# TemperatureModule.net
KiCad netlist of a schematic drawn in EAGLE
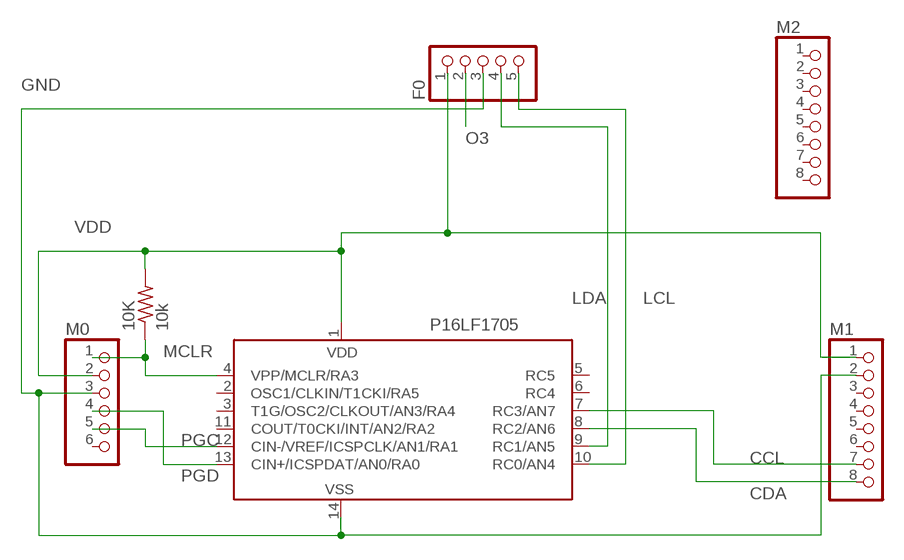
[diagram p0: schematic, sheet 1]

(export (version "E")
  (design (tool "Eeschema 10.0.6"))
  (components
    (comp (ref "10K")
      (value "10k")
      (footprint "eagle-import:0204_7")
      (libsource (lib "eagle-import") (part "R-US_0204/7"))
    )
    (comp (ref "F0")
      (value "PINHD-1X5")
      (footprint "eagle-import:1X05")
      (libsource (lib "eagle-import") (part "PINHD-1X5"))
    )
    (comp (ref "M0")
      (value "PINHD-1X6")
      (footprint "eagle-import:1X06")
      (libsource (lib "eagle-import") (part "PINHD-1X6"))
    )
    (comp (ref "M1")
      (value "PINHD-1X8")
      (footprint "eagle-import:1X08")
      (libsource (lib "eagle-import") (part "PINHD-1X8"))
    )
    (comp (ref "M2")
      (value "PINHD-1X8")
      (footprint "eagle-import:1X08")
      (libsource (lib "eagle-import") (part "PINHD-1X8"))
    )
    (comp (ref "P16LF1705")
      (value "PIC16F676SL")
      (footprint "eagle-import:SO-14")
      (fields (field (name "MF") "MICROCHIP") (field (name "MPN") "PIC16F676-I/SL"))
      (libsource (lib "eagle-import") (part "PIC16F676SL"))
    )
  )
  (nets
    (net (code "1") (name "/CCL") (class "Default")
      (node (ref "M1") (pin "7") (pinfunction "7_7") (pintype "passive"))
      (node (ref "P16LF1705") (pin "7") (pinfunction "RC3/AN7_7") (pintype "bidirectional"))
    )
    (net (code "2") (name "/CDA") (class "Default")
      (node (ref "M1") (pin "8") (pinfunction "8_8") (pintype "passive"))
      (node (ref "P16LF1705") (pin "8") (pinfunction "RC2/AN6_8") (pintype "bidirectional"))
    )
    (net (code "3") (name "/GND") (class "Default")
      (node (ref "F0") (pin "3") (pinfunction "3_3") (pintype "passive"))
      (node (ref "M0") (pin "3") (pinfunction "3_3") (pintype "passive"))
      (node (ref "M1") (pin "2") (pinfunction "2_2") (pintype "passive"))
      (node (ref "P16LF1705") (pin "14") (pinfunction "VSS_14") (pintype "power_in"))
    )
    (net (code "4") (name "/LCL") (class "Default")
      (node (ref "F0") (pin "5") (pinfunction "5_5") (pintype "passive"))
      (node (ref "P16LF1705") (pin "10") (pinfunction "RC0/AN4_10") (pintype "bidirectional"))
    )
    (net (code "5") (name "/LDA") (class "Default")
      (node (ref "F0") (pin "4") (pinfunction "4_4") (pintype "passive"))
      (node (ref "P16LF1705") (pin "9") (pinfunction "RC1/AN5_9") (pintype "bidirectional"))
    )
    (net (code "6") (name "/MCLR") (class "Default")
      (node (ref "10K") (pin "1") (pinfunction "1_1") (pintype "passive"))
      (node (ref "M0") (pin "1") (pinfunction "1_1") (pintype "passive"))
      (node (ref "P16LF1705") (pin "4") (pinfunction "VPP/MCLR/RA3_4") (pintype "input"))
    )
    (net (code "7") (name "/O3") (class "Default")
      (node (ref "F0") (pin "2") (pinfunction "2_2") (pintype "passive"))
    )
    (net (code "8") (name "/PGC") (class "Default")
      (node (ref "M0") (pin "5") (pinfunction "5_5") (pintype "passive"))
      (node (ref "P16LF1705") (pin "12") (pinfunction "CIN-/VREF/ICSPCLK/AN1/RA1_12") (pintype "bidirectional"))
    )
    (net (code "9") (name "/PGD") (class "Default")
      (node (ref "M0") (pin "4") (pinfunction "4_4") (pintype "passive"))
      (node (ref "P16LF1705") (pin "13") (pinfunction "CIN+/ICSPDAT/AN0/RA0_13") (pintype "bidirectional"))
    )
    (net (code "10") (name "/VDD") (class "Default")
      (node (ref "10K") (pin "2") (pinfunction "2_2") (pintype "passive"))
      (node (ref "F0") (pin "1") (pinfunction "1_1") (pintype "passive"))
      (node (ref "M0") (pin "2") (pinfunction "2_2") (pintype "passive"))
      (node (ref "M1") (pin "1") (pinfunction "1_1") (pintype "passive"))
      (node (ref "P16LF1705") (pin "1") (pinfunction "VDD_1") (pintype "power_in"))
    )
    (net (code "11") (name "unconnected-(M0-Pad6)") (class "Default")
      (node (ref "M0") (pin "6") (pinfunction "6_6") (pintype "passive"))
    )
    (net (code "12") (name "unconnected-(M1-Pad3)") (class "Default")
      (node (ref "M1") (pin "3") (pinfunction "3_3") (pintype "passive"))
    )
    (net (code "13") (name "unconnected-(M1-Pad4)") (class "Default")
      (node (ref "M1") (pin "4") (pinfunction "4_4") (pintype "passive"))
    )
    (net (code "14") (name "unconnected-(M1-Pad5)") (class "Default")
      (node (ref "M1") (pin "5") (pinfunction "5_5") (pintype "passive"))
    )
    (net (code "15") (name "unconnected-(M1-Pad6)") (class "Default")
      (node (ref "M1") (pin "6") (pinfunction "6_6") (pintype "passive"))
    )
    (net (code "16") (name "unconnected-(M2-Pad1)") (class "Default")
      (node (ref "M2") (pin "1") (pinfunction "1_1") (pintype "passive"))
    )
    (net (code "17") (name "unconnected-(M2-Pad2)") (class "Default")
      (node (ref "M2") (pin "2") (pinfunction "2_2") (pintype "passive"))
    )
    (net (code "18") (name "unconnected-(M2-Pad3)") (class "Default")
      (node (ref "M2") (pin "3") (pinfunction "3_3") (pintype "passive"))
    )
    (net (code "19") (name "unconnected-(M2-Pad4)") (class "Default")
      (node (ref "M2") (pin "4") (pinfunction "4_4") (pintype "passive"))
    )
    (net (code "20") (name "unconnected-(M2-Pad5)") (class "Default")
      (node (ref "M2") (pin "5") (pinfunction "5_5") (pintype "passive"))
    )
    (net (code "21") (name "unconnected-(M2-Pad6)") (class "Default")
      (node (ref "M2") (pin "6") (pinfunction "6_6") (pintype "passive"))
    )
    (net (code "22") (name "unconnected-(M2-Pad7)") (class "Default")
      (node (ref "M2") (pin "7") (pinfunction "7_7") (pintype "passive"))
    )
    (net (code "23") (name "unconnected-(M2-Pad8)") (class "Default")
      (node (ref "M2") (pin "8") (pinfunction "8_8") (pintype "passive"))
    )
    (net (code "24") (name "unconnected-(P16LF1705-COUT{slash}T0CKI{slash}INT{slash}AN2{slash}RA2-Pad11)") (class "Default")
      (node (ref "P16LF1705") (pin "11") (pinfunction "COUT/T0CKI/INT/AN2/RA2_11") (pintype "bidirectional"))
    )
    (net (code "25") (name "unconnected-(P16LF1705-OSC1{slash}CLKIN{slash}T1CKI{slash}RA5-Pad2)") (class "Default")
      (node (ref "P16LF1705") (pin "2") (pinfunction "OSC1/CLKIN/T1CKI/RA5_2") (pintype "bidirectional"))
    )
    (net (code "26") (name "unconnected-(P16LF1705-RC4-Pad6)") (class "Default")
      (node (ref "P16LF1705") (pin "6") (pinfunction "RC4_6") (pintype "bidirectional"))
    )
    (net (code "27") (name "unconnected-(P16LF1705-RC5-Pad5)") (class "Default")
      (node (ref "P16LF1705") (pin "5") (pinfunction "RC5_5") (pintype "bidirectional"))
    )
    (net (code "28") (name "unconnected-(P16LF1705-T1G{slash}OSC2{slash}CLKOUT{slash}AN3{slash}RA4-Pad3)") (class "Default")
      (node (ref "P16LF1705") (pin "3") (pinfunction "T1G/OSC2/CLKOUT/AN3/RA4_3") (pintype "bidirectional"))
    )
  )
)
